# 1-Schematic_PADAUK_Programmer.net
KiCad netlist of a schematic drawn in EasyEDA
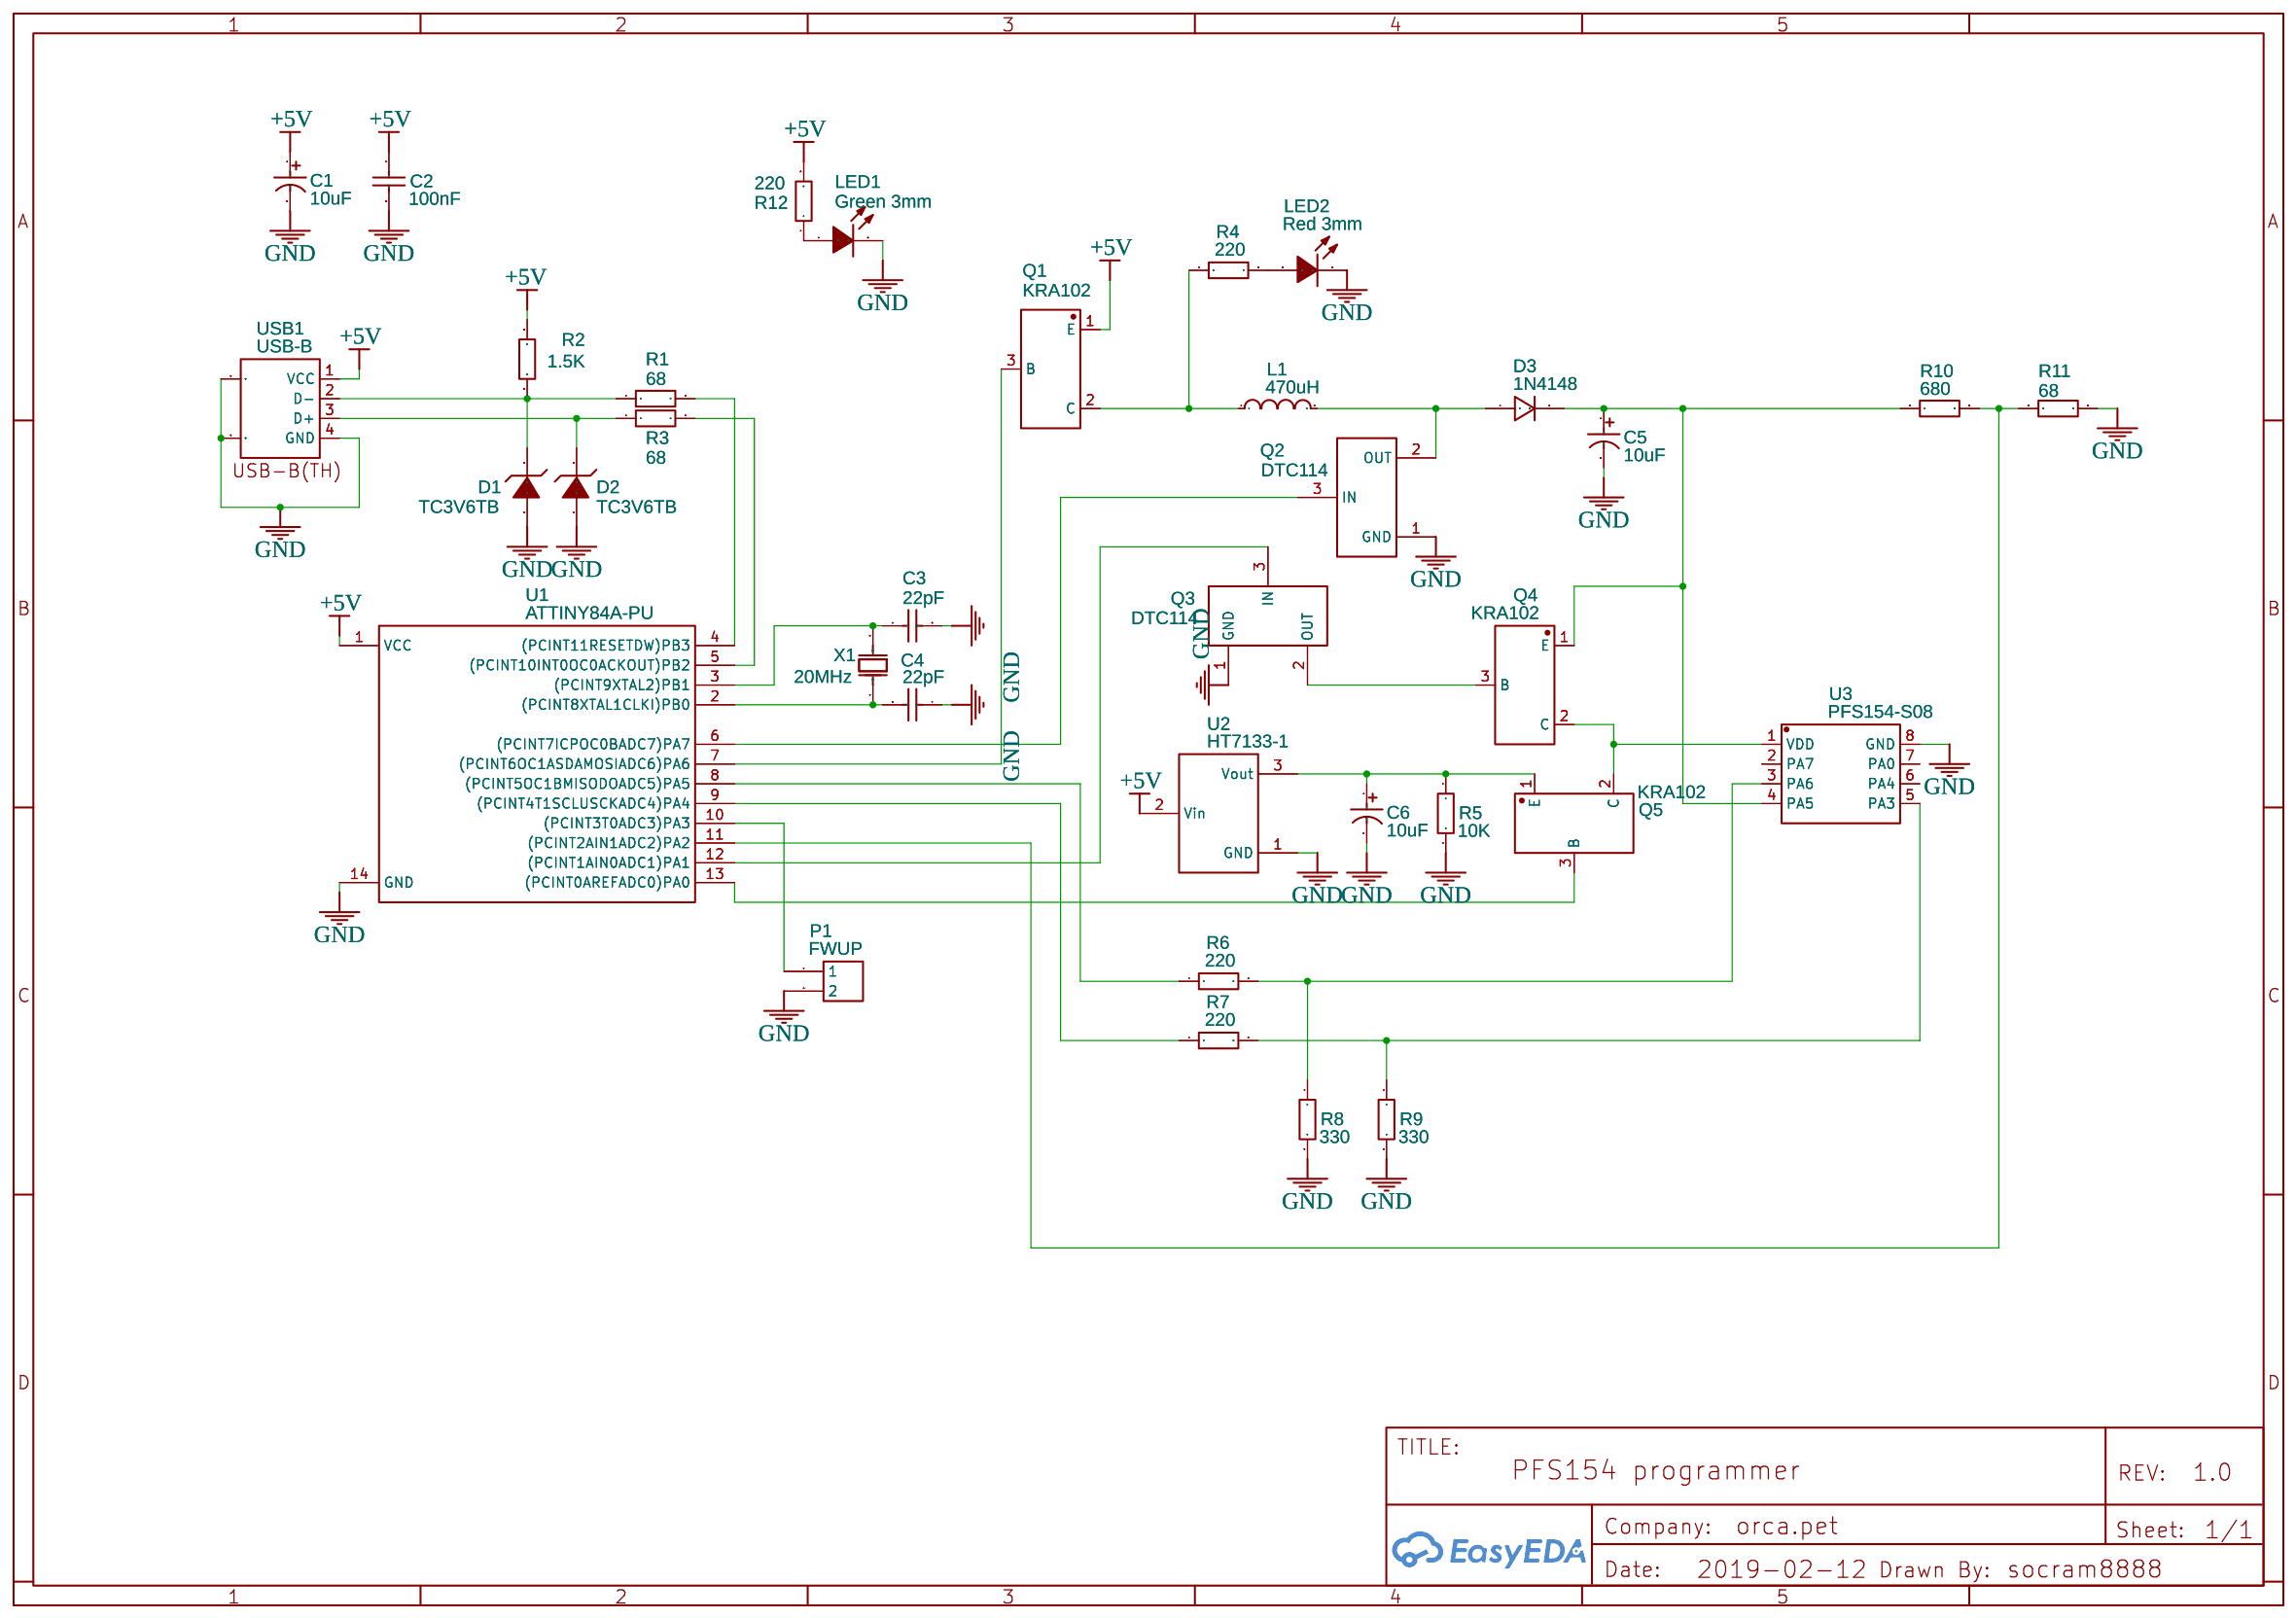
[diagram p0: schematic sheet]

(export (version "E")
  (design (tool "Eeschema 10.0.6"))
  (components
    (comp (ref "C1")
      (value "10uF")
      (fields
        (field (name "BOM_Manufacturer Part") "10uF 25V 4*7")
        (field (name "BOM_Supplier Part") "C43351")
      )
      (libsource (lib "") (part "10uF 25V 4*7"))
    )
    (comp (ref "C2")
      (value "100nF")
      (fields
        (field (name "BOM_Manufacturer Part") "C322C104K2R5TA7301")
        (field (name "BOM_Supplier Part") "C236030")
      )
      (libsource (lib "") (part "C322C104K2R5TA7301"))
    )
    (comp (ref "C3")
      (value "22pF")
      (fields
        (field (name "BOM_Manufacturer Part") "22pf/50V 10%")
        (field (name "BOM_Supplier Part") "C9316")
      )
      (libsource (lib "") (part "22pf/50V 10%"))
    )
    (comp (ref "C4")
      (value "22pF")
      (fields
        (field (name "BOM_Manufacturer Part") "22pf/50V 10%")
        (field (name "BOM_Supplier Part") "C9316")
      )
      (libsource (lib "") (part "22pf/50V 10%_1"))
    )
    (comp (ref "C5")
      (value "10uF")
      (fields
        (field (name "BOM_Manufacturer Part") "10uF 25V 4*7")
        (field (name "BOM_Supplier Part") "C43351")
      )
      (libsource (lib "") (part "10uF 25V 4*7"))
    )
    (comp (ref "C6")
      (value "10uF")
      (fields
        (field (name "BOM_Manufacturer Part") "10uF 25V 4*7")
        (field (name "BOM_Supplier Part") "C43351")
      )
      (libsource (lib "") (part "10uF 25V 4*7"))
    )
    (comp (ref "D1")
      (value "TC3V6TB")
      (fields (field (name "BOM_Supplier Part") "C261195"))
      (libsource (lib "") (part "Unknown_260_240"))
    )
    (comp (ref "D2")
      (value "TC3V6TB")
      (fields (field (name "BOM_Supplier Part") "C261195"))
      (libsource (lib "") (part "Unknown_285_240"))
    )
    (comp (ref "D3")
      (value "1N4148")
      (fields (field (name "BOM_Supplier Part") "C163750"))
      (libsource (lib "") (part "Unknown_765_200"))
    )
    (comp (ref "L1")
      (value "470uH")
      (fields
        (field (name "BOM_Manufacturer Part") "VLU0810-471K")
        (field (name "BOM_Supplier Part") "C72619")
      )
      (libsource (lib "") (part "VLU0810-471K"))
    )
    (comp (ref "LED1")
      (value "Green 3mm")
      (fields
        (field (name "BOM_Manufacturer Part") "LEDOrange orange 3AO4UD")
        (field (name "BOM_Supplier Part") "C62095")
      )
      (libsource (lib "") (part "Unknown_420_110"))
    )
    (comp (ref "LED2")
      (value "Red 3mm")
      (fields
        (field (name "BOM_Manufacturer Part") "LEDOrange orange 3AO4UD")
        (field (name "BOM_Supplier Part") "C62095")
      )
      (libsource (lib "") (part "Unknown_655_125"))
    )
    (comp (ref "P1")
      (value "FWUP")
      (fields
        (field (name "BOM_Manufacturer Part") "2.54mm 1*2P")
        (field (name "BOM_Supplier Part") "C36717")
      )
      (libsource (lib "") (part "Unknown_410_490"))
    )
    (comp (ref "Q1")
      (value "KRA102")
      (fields
        (field (name "BOM_Manufacturer Part") "KRA102-AT/P")
        (field (name "BOM_Supplier Part") "C147284")
      )
      (libsource (lib "") (part "Unknown_525_180"))
    )
    (comp (ref "Q2")
      (value "DTC114")
      (fields
        (field (name "BOM_Manufacturer Part") "DTC114EL-T92-K")
        (field (name "BOM_Supplier Part") "C171504")
      )
      (libsource (lib "") (part "Unknown_685_245"))
    )
    (comp (ref "Q3")
      (value "DTC114")
      (fields
        (field (name "BOM_Manufacturer Part") "DTC114EL-T92-K")
        (field (name "BOM_Supplier Part") "C171504")
      )
      (libsource (lib "") (part "Unknown_635_305"))
    )
    (comp (ref "Q4")
      (value "KRA102")
      (fields
        (field (name "BOM_Manufacturer Part") "KRA102-AT/P")
        (field (name "BOM_Supplier Part") "C147284")
      )
      (libsource (lib "") (part "Unknown_765_340"))
    )
    (comp (ref "Q5")
      (value "KRA102")
      (fields
        (field (name "BOM_Manufacturer Part") "KRA102-AT/P")
        (field (name "BOM_Supplier Part") "C147284")
      )
      (libsource (lib "") (part "Unknown_790_410"))
    )
    (comp (ref "R1")
      (value "68")
      (fields
        (field (name "BOM_Manufacturer Part") "MFR-25FTE52-68R")
        (field (name "BOM_Supplier Part") "C173041")
      )
      (libsource (lib "") (part "MFR-25FTE52-68R"))
    )
    (comp (ref "R2")
      (value "1.5K")
      (fields
        (field (name "BOM_Manufacturer Part") "MF1/8W-1.5KΩ±1% T52")
        (field (name "BOM_Supplier Part") "C119183")
      )
      (libsource (lib "") (part "MF1/8W-1.5KΩ±1% T52"))
    )
    (comp (ref "R3")
      (value "68")
      (fields
        (field (name "BOM_Manufacturer Part") "MFR-25FTE52-68R")
        (field (name "BOM_Supplier Part") "C173041")
      )
      (libsource (lib "") (part "MFR-25FTE52-68R"))
    )
    (comp (ref "R4")
      (value "220")
      (fields (field (name "BOM_Supplier Part") "C337127"))
      (libsource (lib "") (part "MF1/8W ±1% 220Ω OTB5"))
    )
    (comp (ref "R5")
      (value "10K")
      (fields (field (name "BOM_Supplier Part") "C119347"))
      (libsource (lib "") (part "MF1/4W-10KΩ±1% T52"))
    )
    (comp (ref "R6")
      (value "220")
      (fields (field (name "BOM_Supplier Part") "C337127"))
      (libsource (lib "") (part "MF1/8W ±1% 220Ω OTB5"))
    )
    (comp (ref "R7")
      (value "220")
      (fields (field (name "BOM_Supplier Part") "C337127"))
      (libsource (lib "") (part "MF1/8W ±1% 220Ω OTB5"))
    )
    (comp (ref "R8")
      (value "330")
      (fields
        (field (name "BOM_Manufacturer Part") "MFR0W8F3300A50")
        (field (name "BOM_Supplier Part") "C81959")
      )
      (libsource (lib "") (part "MFR0W8F3300A50"))
    )
    (comp (ref "R9")
      (value "330")
      (fields
        (field (name "BOM_Manufacturer Part") "MFR0W8F3300A50")
        (field (name "BOM_Supplier Part") "C81959")
      )
      (libsource (lib "") (part "MFR0W8F3300A50"))
    )
    (comp (ref "R10")
      (value "680")
      (fields
        (field (name "BOM_Manufacturer Part") "MFR-25FTE52-680K")
        (field (name "BOM_Supplier Part") "C173038")
      )
      (libsource (lib "") (part "MFR-25FTE52-680K"))
    )
    (comp (ref "R11")
      (value "68")
      (fields
        (field (name "BOM_Manufacturer Part") "MFR-25FTE52-68R")
        (field (name "BOM_Supplier Part") "C173041")
      )
      (libsource (lib "") (part "MFR-25FTE52-68R"))
    )
    (comp (ref "R12")
      (value "220")
      (fields (field (name "BOM_Supplier Part") "C337127"))
      (libsource (lib "") (part "MF1/8W ±1% 220Ω OTB5_1"))
    )
    (comp (ref "U1")
      (value "ATTINY84A-PU")
      (fields (field (name "BOM_Supplier Part") "C145560"))
      (libsource (lib "") (part "Unknown_265_380"))
    )
    (comp (ref "U2")
      (value "HT7133-1")
      (fields (field (name "BOM_Supplier Part") "C73730"))
      (libsource (lib "") (part "Unknown_610_405"))
    )
    (comp (ref "U3")
      (value "PFS154-S08")
      (fields (field (name "BOM_Supplier Part") "C317611"))
      (libsource (lib "") (part "Unknown_925_385"))
    )
    (comp (ref "USB1")
      (value "USB-B")
      (fields
        (field (name "BOM_Manufacturer Part") "USB-B-Female-90-TH")
        (field (name "BOM_Supplier Part") "C46393")
      )
      (libsource (lib "") (part "Unknown_135_210"))
    )
    (comp (ref "X1")
      (value "20MHz")
      (fields
        (field (name "BOM_Manufacturer Part") "X49SD20MPB2SC")
        (field (name "BOM_Supplier Part") "C21499")
      )
      (libsource (lib "") (part "X49SD20MPB2SC"))
    )
  )
  (nets
    (net (code "1") (name "+5V") (class "Default")
      (node (ref "C1") (pin "1") (pinfunction "1_1") (pintype "input"))
      (node (ref "C2") (pin "1") (pinfunction "1_1") (pintype "input"))
      (node (ref "Q1") (pin "1") (pinfunction "E_1") (pintype "unspecified"))
      (node (ref "R12") (pin "2") (pinfunction "2_2") (pintype "unspecified"))
      (node (ref "R2") (pin "1") (pinfunction "1_1") (pintype "input"))
      (node (ref "U1") (pin "1") (pinfunction "VCC_1") (pintype "unspecified"))
      (node (ref "U2") (pin "2") (pinfunction "Vin_2") (pintype "unspecified"))
      (node (ref "USB1") (pin "1") (pinfunction "VCC_1") (pintype "input"))
    )
    (net (code "2") (name "GND") (class "Default")
      (node (ref "C1") (pin "2") (pinfunction "2_2") (pintype "input"))
      (node (ref "C2") (pin "2") (pinfunction "2_2") (pintype "input"))
      (node (ref "C3") (pin "2") (pinfunction "2_2") (pintype "input"))
      (node (ref "C4") (pin "1") (pinfunction "1_1") (pintype "input"))
      (node (ref "C5") (pin "2") (pinfunction "2_2") (pintype "input"))
      (node (ref "C6") (pin "2") (pinfunction "2_2") (pintype "input"))
      (node (ref "D1") (pin "1") (pinfunction "A_1") (pintype "unspecified"))
      (node (ref "D2") (pin "1") (pinfunction "A_1") (pintype "unspecified"))
      (node (ref "LED1") (pin "2") (pinfunction "K_2") (pintype "unspecified"))
      (node (ref "LED2") (pin "2") (pinfunction "K_2") (pintype "unspecified"))
      (node (ref "P1") (pin "2") (pinfunction "2_2") (pintype "input"))
      (node (ref "Q2") (pin "1") (pinfunction "GND_1") (pintype "unspecified"))
      (node (ref "Q3") (pin "1") (pinfunction "GND_1") (pintype "unspecified"))
      (node (ref "R11") (pin "2") (pinfunction "2_2") (pintype "unspecified"))
      (node (ref "R5") (pin "2") (pinfunction "2_2") (pintype "unspecified"))
      (node (ref "R8") (pin "2") (pinfunction "2_2") (pintype "unspecified"))
      (node (ref "R9") (pin "2") (pinfunction "2_2") (pintype "unspecified"))
      (node (ref "U1") (pin "14") (pinfunction "GND_14") (pintype "unspecified"))
      (node (ref "U2") (pin "1") (pinfunction "GND_1") (pintype "unspecified"))
      (node (ref "U3") (pin "8") (pinfunction "GND_8") (pintype "unspecified"))
      (node (ref "USB1") (pin "0") (pinfunction "0_0") (pintype "unspecified"))
      (node (ref "USB1") (pin "4") (pinfunction "GND_4") (pintype "input"))
    )
    (net (code "3") (name "Net-(D1-K)") (class "Default")
      (node (ref "D1") (pin "2") (pinfunction "K_2") (pintype "unspecified"))
      (node (ref "R1") (pin "1") (pinfunction "1_1") (pintype "unspecified"))
      (node (ref "R2") (pin "2") (pinfunction "2_2") (pintype "input"))
      (node (ref "USB1") (pin "2") (pinfunction "D-_2") (pintype "input"))
    )
    (net (code "4") (name "Net-(D2-K)") (class "Default")
      (node (ref "D2") (pin "2") (pinfunction "K_2") (pintype "unspecified"))
      (node (ref "R3") (pin "1") (pinfunction "1_1") (pintype "unspecified"))
      (node (ref "USB1") (pin "3") (pinfunction "D+_3") (pintype "input"))
    )
    (net (code "5") (name "Net-(LED1-A)") (class "Default")
      (node (ref "LED1") (pin "1") (pinfunction "A_1") (pintype "unspecified"))
      (node (ref "R12") (pin "1") (pinfunction "1_1") (pintype "unspecified"))
    )
    (net (code "6") (name "Net-(LED2-A)") (class "Default")
      (node (ref "LED2") (pin "1") (pinfunction "A_1") (pintype "unspecified"))
      (node (ref "R4") (pin "2") (pinfunction "2_2") (pintype "unspecified"))
    )
    (net (code "7") (name "Net-(Q1-B)") (class "Default")
      (node (ref "Q1") (pin "3") (pinfunction "B_3") (pintype "unspecified"))
      (node (ref "U1") (pin "7") (pinfunction "(PCINT6OC1ASDAMOSIADC6)PA6_7") (pintype "unspecified"))
    )
    (net (code "8") (name "Net-(Q1-C)") (class "Default")
      (node (ref "L1") (pin "1") (pinfunction "1_1") (pintype "unspecified"))
      (node (ref "Q1") (pin "2") (pinfunction "C_2") (pintype "unspecified"))
      (node (ref "R4") (pin "1") (pinfunction "1_1") (pintype "unspecified"))
    )
    (net (code "9") (name "Net-(Q2-IN)") (class "Default")
      (node (ref "Q2") (pin "3") (pinfunction "IN_3") (pintype "unspecified"))
      (node (ref "U1") (pin "6") (pinfunction "(PCINT7ICPOC0BADC7)PA7_6") (pintype "unspecified"))
    )
    (net (code "10") (name "Net-(Q2-OUT)") (class "Default")
      (node (ref "D3") (pin "1") (pinfunction "1_1") (pintype "unspecified"))
      (node (ref "L1") (pin "2") (pinfunction "2_2") (pintype "unspecified"))
      (node (ref "Q2") (pin "2") (pinfunction "OUT_2") (pintype "unspecified"))
    )
    (net (code "11") (name "Net-(Q3-IN)") (class "Default")
      (node (ref "Q3") (pin "3") (pinfunction "IN_3") (pintype "unspecified"))
      (node (ref "U1") (pin "12") (pinfunction "(PCINT1AIN0ADC1)PA1_12") (pintype "unspecified"))
    )
    (net (code "12") (name "Net-(Q3-OUT)") (class "Default")
      (node (ref "Q3") (pin "2") (pinfunction "OUT_2") (pintype "unspecified"))
      (node (ref "Q4") (pin "3") (pinfunction "B_3") (pintype "unspecified"))
    )
    (net (code "13") (name "Net-(Q4-C)") (class "Default")
      (node (ref "Q4") (pin "2") (pinfunction "C_2") (pintype "unspecified"))
      (node (ref "Q5") (pin "2") (pinfunction "C_2") (pintype "unspecified"))
      (node (ref "U3") (pin "1") (pinfunction "VDD_1") (pintype "unspecified"))
    )
    (net (code "14") (name "Net-(Q4-E)") (class "Default")
      (node (ref "C5") (pin "1") (pinfunction "1_1") (pintype "input"))
      (node (ref "D3") (pin "2") (pinfunction "2_2") (pintype "unspecified"))
      (node (ref "Q4") (pin "1") (pinfunction "E_1") (pintype "unspecified"))
      (node (ref "R10") (pin "1") (pinfunction "1_1") (pintype "unspecified"))
      (node (ref "U3") (pin "4") (pinfunction "PA5_4") (pintype "unspecified"))
    )
    (net (code "15") (name "Net-(Q5-B)") (class "Default")
      (node (ref "Q5") (pin "3") (pinfunction "B_3") (pintype "unspecified"))
      (node (ref "U1") (pin "13") (pinfunction "(PCINT0AREFADC0)PA0_13") (pintype "unspecified"))
    )
    (net (code "16") (name "Net-(Q5-E)") (class "Default")
      (node (ref "C6") (pin "1") (pinfunction "1_1") (pintype "input"))
      (node (ref "Q5") (pin "1") (pinfunction "E_1") (pintype "unspecified"))
      (node (ref "R5") (pin "1") (pinfunction "1_1") (pintype "unspecified"))
      (node (ref "U2") (pin "3") (pinfunction "Vout_3") (pintype "unspecified"))
    )
    (net (code "17") (name "Net-(U1-(PCINT2AIN1ADC2)PA2)") (class "Default")
      (node (ref "R10") (pin "2") (pinfunction "2_2") (pintype "unspecified"))
      (node (ref "R11") (pin "1") (pinfunction "1_1") (pintype "unspecified"))
      (node (ref "U1") (pin "11") (pinfunction "(PCINT2AIN1ADC2)PA2_11") (pintype "unspecified"))
    )
    (net (code "18") (name "Net-(U1-(PCINT3T0ADC3)PA3)") (class "Default")
      (node (ref "P1") (pin "1") (pinfunction "1_1") (pintype "input"))
      (node (ref "U1") (pin "10") (pinfunction "(PCINT3T0ADC3)PA3_10") (pintype "unspecified"))
    )
    (net (code "19") (name "Net-(U1-(PCINT4T1SCLUSCKADC4)PA4)") (class "Default")
      (node (ref "R7") (pin "1") (pinfunction "1_1") (pintype "unspecified"))
      (node (ref "U1") (pin "9") (pinfunction "(PCINT4T1SCLUSCKADC4)PA4_9") (pintype "unspecified"))
    )
    (net (code "20") (name "Net-(U1-(PCINT5OC1BMISODOADC5)PA5)") (class "Default")
      (node (ref "R6") (pin "1") (pinfunction "1_1") (pintype "unspecified"))
      (node (ref "U1") (pin "8") (pinfunction "(PCINT5OC1BMISODOADC5)PA5_8") (pintype "unspecified"))
    )
    (net (code "21") (name "Net-(U1-(PCINT8XTAL1CLKI)PB0)") (class "Default")
      (node (ref "C4") (pin "2") (pinfunction "2_2") (pintype "input"))
      (node (ref "U1") (pin "2") (pinfunction "(PCINT8XTAL1CLKI)PB0_2") (pintype "unspecified"))
      (node (ref "X1") (pin "1") (pinfunction "OSC1_1") (pintype "input"))
    )
    (net (code "22") (name "Net-(U1-(PCINT9XTAL2)PB1)") (class "Default")
      (node (ref "C3") (pin "1") (pinfunction "1_1") (pintype "input"))
      (node (ref "U1") (pin "3") (pinfunction "(PCINT9XTAL2)PB1_3") (pintype "unspecified"))
      (node (ref "X1") (pin "2") (pinfunction "OSC2_2") (pintype "input"))
    )
    (net (code "23") (name "Net-(U1-(PCINT10INT0OC0ACKOUT)PB2)") (class "Default")
      (node (ref "R3") (pin "2") (pinfunction "2_2") (pintype "unspecified"))
      (node (ref "U1") (pin "5") (pinfunction "(PCINT10INT0OC0ACKOUT)PB2_5") (pintype "unspecified"))
    )
    (net (code "24") (name "Net-(U1-(PCINT11RESETDW)PB3)") (class "Default")
      (node (ref "R1") (pin "2") (pinfunction "2_2") (pintype "unspecified"))
      (node (ref "U1") (pin "4") (pinfunction "(PCINT11RESETDW)PB3_4") (pintype "unspecified"))
    )
    (net (code "25") (name "Net-(U3-PA3)") (class "Default")
      (node (ref "R7") (pin "2") (pinfunction "2_2") (pintype "unspecified"))
      (node (ref "R9") (pin "1") (pinfunction "1_1") (pintype "unspecified"))
      (node (ref "U3") (pin "5") (pinfunction "PA3_5") (pintype "unspecified"))
    )
    (net (code "26") (name "Net-(U3-PA6)") (class "Default")
      (node (ref "R6") (pin "2") (pinfunction "2_2") (pintype "unspecified"))
      (node (ref "R8") (pin "1") (pinfunction "1_1") (pintype "unspecified"))
      (node (ref "U3") (pin "3") (pinfunction "PA6_3") (pintype "unspecified"))
    )
    (net (code "27") (name "unconnected-(U3-PA0-Pad7)") (class "Default")
      (node (ref "U3") (pin "7") (pinfunction "PA0_7") (pintype "unspecified"))
    )
    (net (code "28") (name "unconnected-(U3-PA4-Pad6)") (class "Default")
      (node (ref "U3") (pin "6") (pinfunction "PA4_6") (pintype "unspecified"))
    )
    (net (code "29") (name "unconnected-(U3-PA7-Pad2)") (class "Default")
      (node (ref "U3") (pin "2") (pinfunction "PA7_2") (pintype "unspecified"))
    )
  )
)
